# ADXL345.net
KiCad netlist of a schematic drawn in Altium Designer
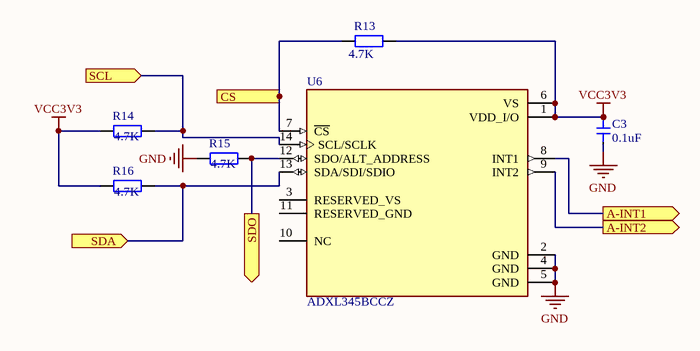
[diagram p0: ADXL345.SchDoc]

(export (version "E")
  (design (tool "Eeschema 10.0.6"))
  (components
    (comp (ref "C3")
      (value "0.1uF")
      (footprint "Cap 0805")
      (description "Capacitor SMD 0805")
      (libsource (lib "Altium_Lib_by_KhueNguyenCreator") (part "Cap 0805"))
    )
    (comp (ref "R13")
      (value "4.7K")
      (footprint "tro smd 0805")
      (description "Dán")
      (libsource (lib "THU VIEN SCH") (part "Tro 0805 1% 0.5R"))
    )
    (comp (ref "R14")
      (value "4.7K")
      (footprint "tro smd 0805")
      (description "Dán")
      (libsource (lib "THU VIEN SCH") (part "Tro 0805 1% 0.5R"))
    )
    (comp (ref "R15")
      (value "4.7K")
      (footprint "tro smd 0805")
      (description "Dán")
      (libsource (lib "THU VIEN SCH") (part "Tro 0805 1% 0.5R"))
    )
    (comp (ref "R16")
      (value "4.7K")
      (footprint "tro smd 0805")
      (description "Dán")
      (libsource (lib "THU VIEN SCH") (part "Tro 0805 1% 0.5R"))
    )
    (comp (ref "U6")
      (value "ADXL345BCCZ")
      (footprint "IC_ADXL345BCCZ")
      (description "3-Axis, Â±2 g/Â±4 g/Â±8 g/Â±16 g Digital Accelerometer")
      (fields (field (name "MF") "Analog Devices"))
      (libsource (lib "ADXL345BCCZ") (part "ADXL345BCCZ"))
    )
  )
  (nets
    (net (code "1") (name "/A-INT1") (class "Default")
      (node (ref "U6") (pin "8") (pinfunction "INT1_8") (pintype "output"))
    )
    (net (code "2") (name "/A-INT2") (class "Default")
      (node (ref "U6") (pin "9") (pinfunction "INT2_9") (pintype "output"))
    )
    (net (code "3") (name "/CS") (class "Default")
      (node (ref "R13") (pin "2") (pinfunction "2_2") (pintype "passive"))
      (node (ref "U6") (pin "7") (pinfunction "~{CS}_7") (pintype "input"))
    )
    (net (code "4") (name "/SCL") (class "Default")
      (node (ref "R14") (pin "1") (pinfunction "1_1") (pintype "passive"))
      (node (ref "U6") (pin "14") (pinfunction "SCL/SCLK_14") (pintype "input"))
    )
    (net (code "5") (name "/SDA") (class "Default")
      (node (ref "R16") (pin "1") (pinfunction "1_1") (pintype "passive"))
      (node (ref "U6") (pin "13") (pinfunction "SDA/SDI/SDIO_13") (pintype "bidirectional"))
    )
    (net (code "6") (name "/SDO") (class "Default")
      (node (ref "R15") (pin "1") (pinfunction "1_1") (pintype "passive"))
      (node (ref "U6") (pin "12") (pinfunction "SDO/ALT_ADDRESS_12") (pintype "bidirectional"))
    )
    (net (code "7") (name "GND") (class "Default")
      (node (ref "C3") (pin "2") (pinfunction "2_2") (pintype "passive"))
      (node (ref "R15") (pin "2") (pinfunction "2_2") (pintype "passive"))
      (node (ref "U6") (pin "2") (pinfunction "GND_2") (pintype "power_in"))
      (node (ref "U6") (pin "4") (pinfunction "GND_4") (pintype "power_in"))
      (node (ref "U6") (pin "5") (pinfunction "GND_5") (pintype "power_in"))
    )
    (net (code "8") (name "VCC3V3") (class "Default")
      (node (ref "C3") (pin "1") (pinfunction "1_1") (pintype "passive"))
      (node (ref "R13") (pin "1") (pinfunction "1_1") (pintype "passive"))
      (node (ref "R14") (pin "2") (pinfunction "2_2") (pintype "passive"))
      (node (ref "R16") (pin "2") (pinfunction "2_2") (pintype "passive"))
      (node (ref "U6") (pin "1") (pinfunction "VDD_I/O_1") (pintype "power_in"))
      (node (ref "U6") (pin "6") (pinfunction "VS_6") (pintype "power_in"))
    )
    (net (code "9") (name "unconnected-(U6-NC-Pad10)") (class "Default")
      (node (ref "U6") (pin "10") (pinfunction "NC_10") (pintype "passive"))
    )
    (net (code "10") (name "unconnected-(U6-RESERVED_GND-Pad11)") (class "Default")
      (node (ref "U6") (pin "11") (pinfunction "RESERVED_GND_11") (pintype "passive"))
    )
    (net (code "11") (name "unconnected-(U6-RESERVED_VS-Pad3)") (class "Default")
      (node (ref "U6") (pin "3") (pinfunction "RESERVED_VS_3") (pintype "passive"))
    )
  )
)
